# ADE7953_WattMeter_breakout_v1_00.net
KiCad netlist of a schematic drawn in EAGLE
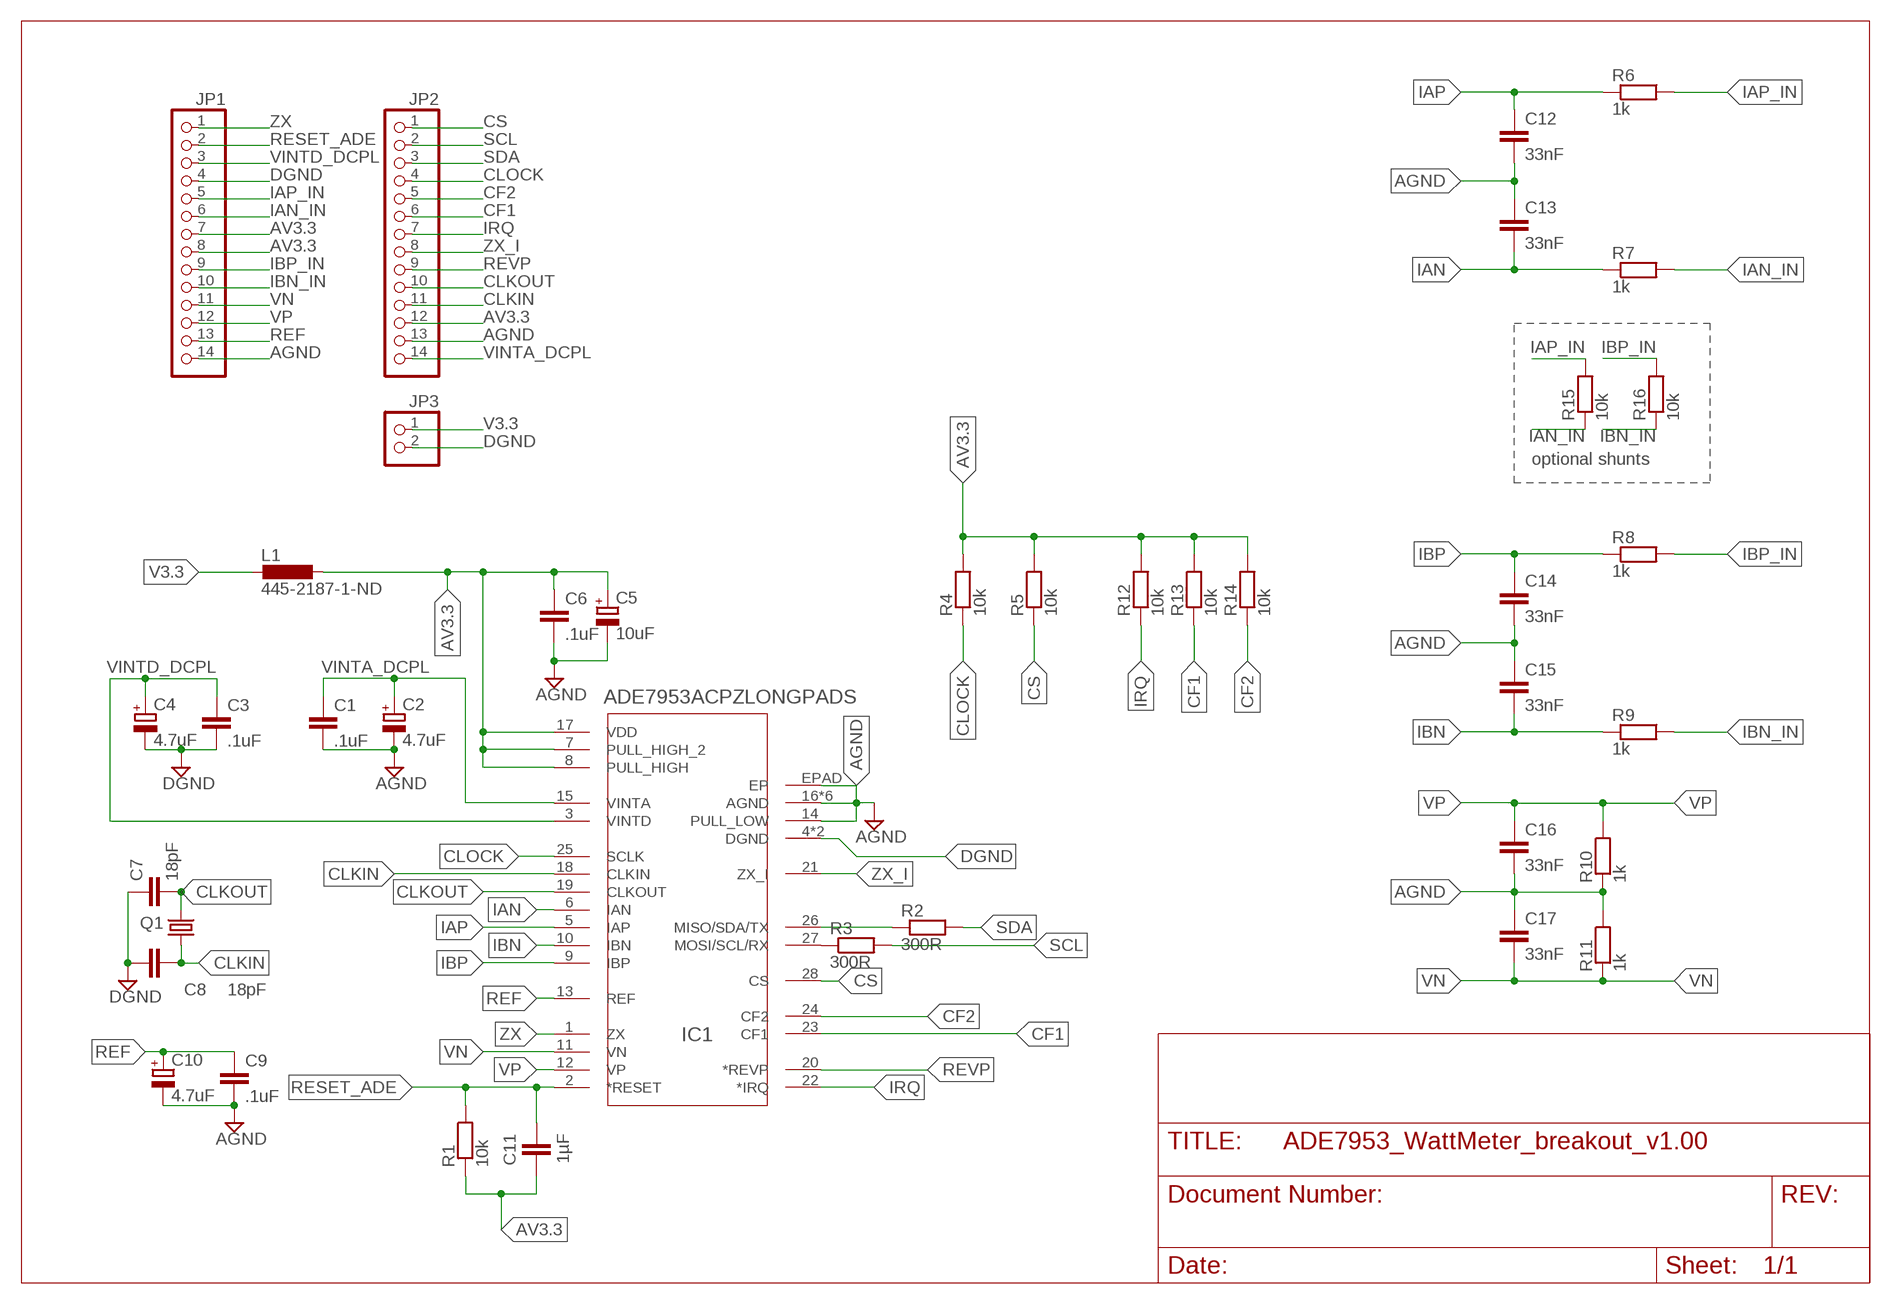
[diagram p0: schematic, sheet 1]

(export (version "E")
  (design (tool "Eeschema 10.0.6"))
  (components
    (comp (ref "C1")
      (value ".1uF")
      (footprint "eagle-import:C0805K@1")
      (libsource (lib "eagle-import") (part "C-EUC0805K"))
    )
    (comp (ref "C2")
      (value "4.7uF")
      (footprint "eagle-import:A_3216-18R")
      (libsource (lib "eagle-import") (part "CPOL-EUA/3216-18R"))
    )
    (comp (ref "C3")
      (value ".1uF")
      (footprint "eagle-import:C0805K@1")
      (libsource (lib "eagle-import") (part "C-EUC0805K"))
    )
    (comp (ref "C4")
      (value "4.7uF")
      (footprint "eagle-import:A_3216-18R")
      (libsource (lib "eagle-import") (part "CPOL-EUA/3216-18R"))
    )
    (comp (ref "C5")
      (value "10uF")
      (footprint "eagle-import:A_3216-18R")
      (libsource (lib "eagle-import") (part "CPOL-EUA/3216-18R"))
    )
    (comp (ref "C6")
      (value ".1uF")
      (footprint "eagle-import:C0805K@1")
      (libsource (lib "eagle-import") (part "C-EUC0805K"))
    )
    (comp (ref "C7")
      (value "18pF")
      (footprint "eagle-import:C0805K@1")
      (libsource (lib "eagle-import") (part "C-EUC0805K"))
    )
    (comp (ref "C8")
      (value "18pF")
      (footprint "eagle-import:C0805K@1")
      (libsource (lib "eagle-import") (part "C-EUC0805K"))
    )
    (comp (ref "C9")
      (value ".1uF")
      (footprint "eagle-import:C0805K@1")
      (libsource (lib "eagle-import") (part "C-EUC0805K"))
    )
    (comp (ref "C10")
      (value "4.7uF")
      (footprint "eagle-import:A_3216-18R")
      (libsource (lib "eagle-import") (part "CPOL-EUA/3216-18R"))
    )
    (comp (ref "C11")
      (value "1µF")
      (footprint "eagle-import:C0805K@1")
      (libsource (lib "eagle-import") (part "C-EUC0805K"))
    )
    (comp (ref "C12")
      (value "33nF")
      (footprint "eagle-import:C0805K@1")
      (libsource (lib "eagle-import") (part "C-EUC0805K"))
    )
    (comp (ref "C13")
      (value "33nF")
      (footprint "eagle-import:C0805K@1")
      (libsource (lib "eagle-import") (part "C-EUC0805K"))
    )
    (comp (ref "C14")
      (value "33nF")
      (footprint "eagle-import:C0805K@1")
      (libsource (lib "eagle-import") (part "C-EUC0805K"))
    )
    (comp (ref "C15")
      (value "33nF")
      (footprint "eagle-import:C0805K@1")
      (libsource (lib "eagle-import") (part "C-EUC0805K"))
    )
    (comp (ref "C16")
      (value "33nF")
      (footprint "eagle-import:C0805K@1")
      (libsource (lib "eagle-import") (part "C-EUC0805K"))
    )
    (comp (ref "C17")
      (value "33nF")
      (footprint "eagle-import:C0805K@1")
      (libsource (lib "eagle-import") (part "C-EUC0805K"))
    )
    (comp (ref "IC1")
      (value "ADE7953ACPZLONGPADS")
      (footprint "eagle-import:VQFN-28-D")
      (libsource (lib "eagle-import") (part "ADE7953ACPZ5.0"))
    )
    (comp (ref "JP1")
      (value "PINHD-1X14")
      (footprint "eagle-import:1X14")
      (libsource (lib "eagle-import") (part "PINHD-1X14"))
    )
    (comp (ref "JP2")
      (value "PINHD-1X14")
      (footprint "eagle-import:1X14")
      (libsource (lib "eagle-import") (part "PINHD-1X14"))
    )
    (comp (ref "JP3")
      (value "PINHD-1X2")
      (footprint "eagle-import:1X02")
      (libsource (lib "eagle-import") (part "PINHD-1X2"))
    )
    (comp (ref "L1")
      (value "445-2187-1-ND")
      (footprint "eagle-import:L2012C")
      (libsource (lib "eagle-import") (part "L-EUL2012C"))
    )
    (comp (ref "Q1")
      (value "535-10200-1-ND")
      (footprint "eagle-import:SM49")
      (libsource (lib "eagle-import") (part "CRYSTALSM49"))
    )
    (comp (ref "R1")
      (value "10k")
      (footprint "eagle-import:R0805@1")
      (libsource (lib "eagle-import") (part "R-US_R0805"))
    )
    (comp (ref "R2")
      (value "300R")
      (footprint "eagle-import:R0805@1")
      (libsource (lib "eagle-import") (part "R-US_R0805"))
    )
    (comp (ref "R3")
      (value "300R")
      (footprint "eagle-import:R0805@1")
      (libsource (lib "eagle-import") (part "R-US_R0805"))
    )
    (comp (ref "R4")
      (value "10k")
      (footprint "eagle-import:R0805@1")
      (libsource (lib "eagle-import") (part "R-US_R0805"))
    )
    (comp (ref "R5")
      (value "10k")
      (footprint "eagle-import:R0805@1")
      (libsource (lib "eagle-import") (part "R-US_R0805"))
    )
    (comp (ref "R6")
      (value "1k")
      (footprint "eagle-import:R0805@1")
      (libsource (lib "eagle-import") (part "R-US_R0805"))
    )
    (comp (ref "R7")
      (value "1k")
      (footprint "eagle-import:R0805@1")
      (libsource (lib "eagle-import") (part "R-US_R0805"))
    )
    (comp (ref "R8")
      (value "1k")
      (footprint "eagle-import:R0805@1")
      (libsource (lib "eagle-import") (part "R-US_R0805"))
    )
    (comp (ref "R9")
      (value "1k")
      (footprint "eagle-import:R0805@1")
      (libsource (lib "eagle-import") (part "R-US_R0805"))
    )
    (comp (ref "R10")
      (value "1k")
      (footprint "eagle-import:R0805@1")
      (libsource (lib "eagle-import") (part "R-US_R0805"))
    )
    (comp (ref "R11")
      (value "1k")
      (footprint "eagle-import:R0805@1")
      (libsource (lib "eagle-import") (part "R-US_R0805"))
    )
    (comp (ref "R12")
      (value "10k")
      (footprint "eagle-import:R0805@1")
      (libsource (lib "eagle-import") (part "R-US_R0805"))
    )
    (comp (ref "R13")
      (value "10k")
      (footprint "eagle-import:R0805@1")
      (libsource (lib "eagle-import") (part "R-US_R0805"))
    )
    (comp (ref "R14")
      (value "10k")
      (footprint "eagle-import:R0805@1")
      (libsource (lib "eagle-import") (part "R-US_R0805"))
    )
    (comp (ref "R15")
      (value "10k")
      (footprint "eagle-import:R0805@1")
      (libsource (lib "eagle-import") (part "R-US_R0805"))
    )
    (comp (ref "R16")
      (value "10k")
      (footprint "eagle-import:R0805@1")
      (libsource (lib "eagle-import") (part "R-US_R0805"))
    )
  )
  (nets
    (net (code "1") (name "/VINTA_DCPL") (class "Default")
      (node (ref "C1") (pin "1") (pinfunction "1_1") (pintype "passive"))
      (node (ref "C2") (pin "+") (pinfunction "+_+") (pintype "passive"))
      (node (ref "IC1") (pin "15") (pinfunction "VINTA_15") (pintype "passive"))
      (node (ref "JP2") (pin "14") (pinfunction "14_14") (pintype "passive"))
    )
    (net (code "2") (name "/VINTD_DCPL") (class "Default")
      (node (ref "C3") (pin "1") (pinfunction "1_1") (pintype "passive"))
      (node (ref "C4") (pin "+") (pinfunction "+_+") (pintype "passive"))
      (node (ref "IC1") (pin "3") (pinfunction "VINTD_3") (pintype "passive"))
      (node (ref "JP1") (pin "3") (pinfunction "3_3") (pintype "passive"))
    )
    (net (code "3") (name "AGND") (class "Default")
      (node (ref "C1") (pin "2") (pinfunction "2_2") (pintype "passive"))
      (node (ref "C10") (pin "-") (pinfunction "-_-") (pintype "passive"))
      (node (ref "C12") (pin "2") (pinfunction "2_2") (pintype "passive"))
      (node (ref "C13") (pin "1") (pinfunction "1_1") (pintype "passive"))
      (node (ref "C14") (pin "2") (pinfunction "2_2") (pintype "passive"))
      (node (ref "C15") (pin "1") (pinfunction "1_1") (pintype "passive"))
      (node (ref "C16") (pin "2") (pinfunction "2_2") (pintype "passive"))
      (node (ref "C17") (pin "1") (pinfunction "1_1") (pintype "passive"))
      (node (ref "C2") (pin "-") (pinfunction "-_-") (pintype "passive"))
      (node (ref "C5") (pin "-") (pinfunction "-_-") (pintype "passive"))
      (node (ref "C6") (pin "2") (pinfunction "2_2") (pintype "passive"))
      (node (ref "C9") (pin "2") (pinfunction "2_2") (pintype "passive"))
      (node (ref "IC1") (pin "14") (pinfunction "PULL_LOW_14") (pintype "passive"))
      (node (ref "IC1") (pin "16") (pinfunction "AGND_16") (pintype "passive"))
      (node (ref "IC1") (pin "29") (pinfunction "AGND_29") (pintype "passive"))
      (node (ref "IC1") (pin "30") (pinfunction "AGND_30") (pintype "passive"))
      (node (ref "IC1") (pin "31") (pinfunction "AGND_31") (pintype "passive"))
      (node (ref "IC1") (pin "32") (pinfunction "AGND_32") (pintype "passive"))
      (node (ref "IC1") (pin "EPAD") (pinfunction "EP_EPAD") (pintype "passive"))
      (node (ref "IC1") (pin "_AGND") (pinfunction "AGND__AGND") (pintype "passive"))
      (node (ref "JP1") (pin "14") (pinfunction "14_14") (pintype "passive"))
      (node (ref "JP2") (pin "13") (pinfunction "13_13") (pintype "passive"))
      (node (ref "R10") (pin "1") (pinfunction "1_1") (pintype "passive"))
      (node (ref "R11") (pin "2") (pinfunction "2_2") (pintype "passive"))
    )
    (net (code "4") (name "AV3.3") (class "Default")
      (node (ref "C11") (pin "2") (pinfunction "2_2") (pintype "passive"))
      (node (ref "C5") (pin "+") (pinfunction "+_+") (pintype "passive"))
      (node (ref "C6") (pin "1") (pinfunction "1_1") (pintype "passive"))
      (node (ref "IC1") (pin "17") (pinfunction "VDD_17") (pintype "passive"))
      (node (ref "IC1") (pin "7") (pinfunction "PULL_HIGH_2_7") (pintype "passive"))
      (node (ref "IC1") (pin "8") (pinfunction "PULL_HIGH_8") (pintype "passive"))
      (node (ref "JP1") (pin "7") (pinfunction "7_7") (pintype "passive"))
      (node (ref "JP1") (pin "8") (pinfunction "8_8") (pintype "passive"))
      (node (ref "JP2") (pin "12") (pinfunction "12_12") (pintype "passive"))
      (node (ref "L1") (pin "1") (pinfunction "1_1") (pintype "passive"))
      (node (ref "R1") (pin "1") (pinfunction "1_1") (pintype "passive"))
      (node (ref "R12") (pin "2") (pinfunction "2_2") (pintype "passive"))
      (node (ref "R13") (pin "2") (pinfunction "2_2") (pintype "passive"))
      (node (ref "R14") (pin "2") (pinfunction "2_2") (pintype "passive"))
      (node (ref "R4") (pin "2") (pinfunction "2_2") (pintype "passive"))
      (node (ref "R5") (pin "2") (pinfunction "2_2") (pintype "passive"))
    )
    (net (code "5") (name "CF1") (class "Default")
      (node (ref "IC1") (pin "23") (pinfunction "CF1_23") (pintype "passive"))
      (node (ref "JP2") (pin "6") (pinfunction "6_6") (pintype "passive"))
      (node (ref "R13") (pin "1") (pinfunction "1_1") (pintype "passive"))
    )
    (net (code "6") (name "CF2") (class "Default")
      (node (ref "IC1") (pin "24") (pinfunction "CF2_24") (pintype "passive"))
      (node (ref "JP2") (pin "5") (pinfunction "5_5") (pintype "passive"))
      (node (ref "R14") (pin "1") (pinfunction "1_1") (pintype "passive"))
    )
    (net (code "7") (name "CLKIN") (class "Default")
      (node (ref "C8") (pin "2") (pinfunction "2_2") (pintype "passive"))
      (node (ref "IC1") (pin "18") (pinfunction "CLKIN_18") (pintype "passive"))
      (node (ref "JP2") (pin "11") (pinfunction "11_11") (pintype "passive"))
      (node (ref "Q1") (pin "1") (pinfunction "1_1") (pintype "passive"))
    )
    (net (code "8") (name "CLKOUT") (class "Default")
      (node (ref "C7") (pin "2") (pinfunction "2_2") (pintype "passive"))
      (node (ref "IC1") (pin "19") (pinfunction "CLKOUT_19") (pintype "passive"))
      (node (ref "JP2") (pin "10") (pinfunction "10_10") (pintype "passive"))
      (node (ref "Q1") (pin "2") (pinfunction "2_2") (pintype "passive"))
    )
    (net (code "9") (name "CLOCK") (class "Default")
      (node (ref "IC1") (pin "25") (pinfunction "SCLK_25") (pintype "passive"))
      (node (ref "JP2") (pin "4") (pinfunction "4_4") (pintype "passive"))
      (node (ref "R4") (pin "1") (pinfunction "1_1") (pintype "passive"))
    )
    (net (code "10") (name "CS") (class "Default")
      (node (ref "IC1") (pin "28") (pinfunction "CS_28") (pintype "passive"))
      (node (ref "JP2") (pin "1") (pinfunction "1_1") (pintype "passive"))
      (node (ref "R5") (pin "1") (pinfunction "1_1") (pintype "passive"))
    )
    (net (code "11") (name "DGND") (class "Default")
      (node (ref "C3") (pin "2") (pinfunction "2_2") (pintype "passive"))
      (node (ref "C4") (pin "-") (pinfunction "-_-") (pintype "passive"))
      (node (ref "C7") (pin "1") (pinfunction "1_1") (pintype "passive"))
      (node (ref "C8") (pin "1") (pinfunction "1_1") (pintype "passive"))
      (node (ref "IC1") (pin "4") (pinfunction "DGND_4") (pintype "passive"))
      (node (ref "IC1") (pin "_DGND") (pinfunction "DGND__DGND") (pintype "passive"))
      (node (ref "JP1") (pin "4") (pinfunction "4_4") (pintype "passive"))
      (node (ref "JP3") (pin "2") (pinfunction "2_2") (pintype "passive"))
    )
    (net (code "12") (name "IAN") (class "Default")
      (node (ref "C13") (pin "2") (pinfunction "2_2") (pintype "passive"))
      (node (ref "IC1") (pin "6") (pinfunction "IAN_6") (pintype "passive"))
      (node (ref "R7") (pin "1") (pinfunction "1_1") (pintype "passive"))
    )
    (net (code "13") (name "IAN_IN") (class "Default")
      (node (ref "JP1") (pin "6") (pinfunction "6_6") (pintype "passive"))
      (node (ref "R15") (pin "1") (pinfunction "1_1") (pintype "passive"))
      (node (ref "R7") (pin "2") (pinfunction "2_2") (pintype "passive"))
    )
    (net (code "14") (name "IAP") (class "Default")
      (node (ref "C12") (pin "1") (pinfunction "1_1") (pintype "passive"))
      (node (ref "IC1") (pin "5") (pinfunction "IAP_5") (pintype "passive"))
      (node (ref "R6") (pin "1") (pinfunction "1_1") (pintype "passive"))
    )
    (net (code "15") (name "IAP_IN") (class "Default")
      (node (ref "JP1") (pin "5") (pinfunction "5_5") (pintype "passive"))
      (node (ref "R15") (pin "2") (pinfunction "2_2") (pintype "passive"))
      (node (ref "R6") (pin "2") (pinfunction "2_2") (pintype "passive"))
    )
    (net (code "16") (name "IBN") (class "Default")
      (node (ref "C15") (pin "2") (pinfunction "2_2") (pintype "passive"))
      (node (ref "IC1") (pin "10") (pinfunction "IBN_10") (pintype "passive"))
      (node (ref "R9") (pin "1") (pinfunction "1_1") (pintype "passive"))
    )
    (net (code "17") (name "IBN_IN") (class "Default")
      (node (ref "JP1") (pin "10") (pinfunction "10_10") (pintype "passive"))
      (node (ref "R16") (pin "1") (pinfunction "1_1") (pintype "passive"))
      (node (ref "R9") (pin "2") (pinfunction "2_2") (pintype "passive"))
    )
    (net (code "18") (name "IBP") (class "Default")
      (node (ref "C14") (pin "1") (pinfunction "1_1") (pintype "passive"))
      (node (ref "IC1") (pin "9") (pinfunction "IBP_9") (pintype "passive"))
      (node (ref "R8") (pin "1") (pinfunction "1_1") (pintype "passive"))
    )
    (net (code "19") (name "IBP_IN") (class "Default")
      (node (ref "JP1") (pin "9") (pinfunction "9_9") (pintype "passive"))
      (node (ref "R16") (pin "2") (pinfunction "2_2") (pintype "passive"))
      (node (ref "R8") (pin "2") (pinfunction "2_2") (pintype "passive"))
    )
    (net (code "20") (name "IRQ") (class "Default")
      (node (ref "IC1") (pin "22") (pinfunction "*IRQ_22") (pintype "passive"))
      (node (ref "JP2") (pin "7") (pinfunction "7_7") (pintype "passive"))
      (node (ref "R12") (pin "1") (pinfunction "1_1") (pintype "passive"))
    )
    (net (code "21") (name "Net-(IC1-MISO{slash}SDA{slash}TX)") (class "Default")
      (node (ref "IC1") (pin "26") (pinfunction "MISO/SDA/TX_26") (pintype "passive"))
      (node (ref "R2") (pin "1") (pinfunction "1_1") (pintype "passive"))
    )
    (net (code "22") (name "Net-(IC1-MOSI{slash}SCL{slash}RX)") (class "Default")
      (node (ref "IC1") (pin "27") (pinfunction "MOSI/SCL/RX_27") (pintype "passive"))
      (node (ref "R3") (pin "1") (pinfunction "1_1") (pintype "passive"))
    )
    (net (code "23") (name "REF") (class "Default")
      (node (ref "C10") (pin "+") (pinfunction "+_+") (pintype "passive"))
      (node (ref "C9") (pin "1") (pinfunction "1_1") (pintype "passive"))
      (node (ref "IC1") (pin "13") (pinfunction "REF_13") (pintype "passive"))
      (node (ref "JP1") (pin "13") (pinfunction "13_13") (pintype "passive"))
    )
    (net (code "24") (name "RESET_ADE") (class "Default")
      (node (ref "C11") (pin "1") (pinfunction "1_1") (pintype "passive"))
      (node (ref "IC1") (pin "2") (pinfunction "*RESET_2") (pintype "passive"))
      (node (ref "JP1") (pin "2") (pinfunction "2_2") (pintype "passive"))
      (node (ref "R1") (pin "2") (pinfunction "2_2") (pintype "passive"))
    )
    (net (code "25") (name "REVP") (class "Default")
      (node (ref "IC1") (pin "20") (pinfunction "*REVP_20") (pintype "passive"))
      (node (ref "JP2") (pin "9") (pinfunction "9_9") (pintype "passive"))
    )
    (net (code "26") (name "SCL") (class "Default")
      (node (ref "JP2") (pin "2") (pinfunction "2_2") (pintype "passive"))
      (node (ref "R3") (pin "2") (pinfunction "2_2") (pintype "passive"))
    )
    (net (code "27") (name "SDA") (class "Default")
      (node (ref "JP2") (pin "3") (pinfunction "3_3") (pintype "passive"))
      (node (ref "R2") (pin "2") (pinfunction "2_2") (pintype "passive"))
    )
    (net (code "28") (name "V3.3") (class "Default")
      (node (ref "JP3") (pin "1") (pinfunction "1_1") (pintype "passive"))
      (node (ref "L1") (pin "2") (pinfunction "2_2") (pintype "passive"))
    )
    (net (code "29") (name "VN") (class "Default")
      (node (ref "C17") (pin "2") (pinfunction "2_2") (pintype "passive"))
      (node (ref "IC1") (pin "11") (pinfunction "VN_11") (pintype "passive"))
      (node (ref "JP1") (pin "11") (pinfunction "11_11") (pintype "passive"))
      (node (ref "R11") (pin "1") (pinfunction "1_1") (pintype "passive"))
    )
    (net (code "30") (name "VP") (class "Default")
      (node (ref "C16") (pin "1") (pinfunction "1_1") (pintype "passive"))
      (node (ref "IC1") (pin "12") (pinfunction "VP_12") (pintype "passive"))
      (node (ref "JP1") (pin "12") (pinfunction "12_12") (pintype "passive"))
      (node (ref "R10") (pin "2") (pinfunction "2_2") (pintype "passive"))
    )
    (net (code "31") (name "ZX") (class "Default")
      (node (ref "IC1") (pin "1") (pinfunction "ZX_1") (pintype "passive"))
      (node (ref "JP1") (pin "1") (pinfunction "1_1") (pintype "passive"))
    )
    (net (code "32") (name "ZX_I") (class "Default")
      (node (ref "IC1") (pin "21") (pinfunction "ZX_I_21") (pintype "passive"))
      (node (ref "JP2") (pin "8") (pinfunction "8_8") (pintype "passive"))
    )
  )
)
